# Drive_Led_Test_Bleu.net
KiCad netlist of a schematic drawn in EAGLE
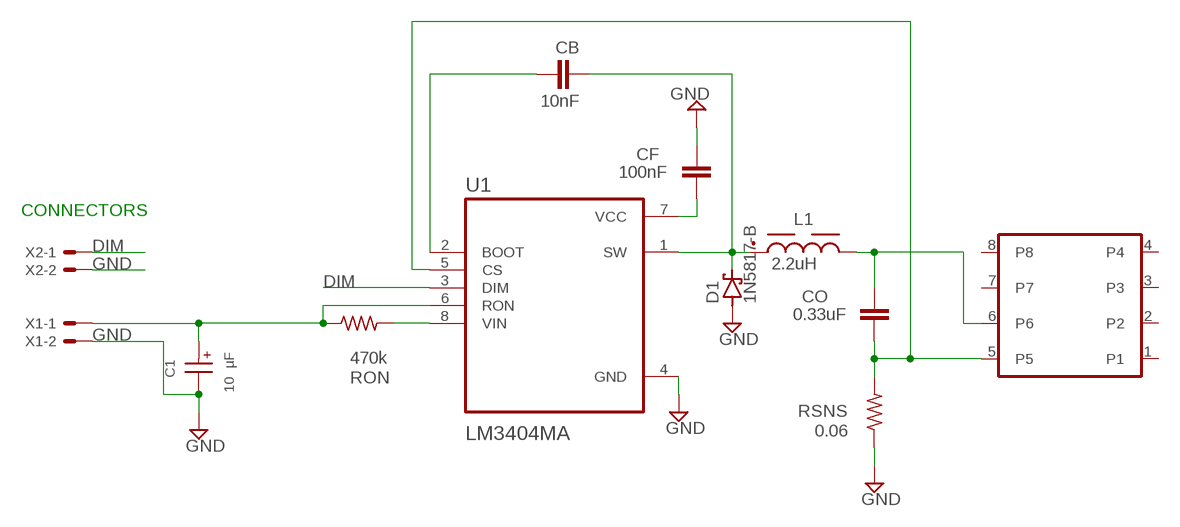
[diagram p0: schematic, sheet 1]

(export (version "E")
  (design (tool "Eeschema 10.0.6"))
  (components
    (comp (ref "C1")
      (value "10 µF")
      (footprint "eagle-import:WCAP-ASLL_4X5.5(DXL)")
      (libsource (lib "eagle-import") (part "WCAP-ASLL_4X5.5_865060440001"))
    )
    (comp (ref "CB")
      (value "10nF")
      (footprint "eagle-import:C0603")
      (libsource (lib "eagle-import") (part "C-EUC0603"))
    )
    (comp (ref "CF")
      (value "100nF")
      (footprint "eagle-import:C0603")
      (libsource (lib "eagle-import") (part "C-EUC0603"))
    )
    (comp (ref "CO")
      (value "0.33uF")
      (footprint "eagle-import:C0603")
      (libsource (lib "eagle-import") (part "C-EUC0603"))
    )
    (comp (ref "D1")
      (value "1N5817-B")
      (footprint "eagle-import:DO41-7.6")
      (libsource (lib "eagle-import") (part "1N5817-B"))
    )
    (comp (ref "L1")
      (value "2.2uH")
      (footprint "eagle-import:WE-PDA_1260")
      (libsource (lib "eagle-import") (part "WE-PDA_1260_784771022"))
    )
    (comp (ref "RON")
      (value "470k")
      (footprint "eagle-import:R0603")
      (libsource (lib "eagle-import") (part "R-US_R0603"))
    )
    (comp (ref "RSNS")
      (value "0.06")
      (footprint "eagle-import:R0603")
      (libsource (lib "eagle-import") (part "R-US_R0603"))
    )
    (comp (ref "U$1")
      (value "LE_RTDUW_S2WM_DEVICE")
      (footprint "eagle-import:LE_RTDUW_S2WM_FOOTPRINT")
      (libsource (lib "eagle-import") (part "LE_RTDUW_S2WM_DEVICE"))
    )
    (comp (ref "U1")
      (value "LM3404MA")
      (footprint "eagle-import:SOIC127P599X175-8N")
      (fields (field (name "MF") "Texas Instruments") (field (name "MP") "LM3404MA/NOPB"))
      (libsource (lib "eagle-import") (part "LM3404MA"))
    )
    (comp (ref "X1")
      (value "22-23-2021")
      (footprint "eagle-import:22-23-2021")
      (fields (field (name "MF") "MOLEX"))
      (libsource (lib "eagle-import") (part "22-23-2021"))
    )
    (comp (ref "X2")
      (value "22-23-2021")
      (footprint "eagle-import:22-23-2021")
      (fields (field (name "MF") "MOLEX"))
      (libsource (lib "eagle-import") (part "22-23-2021"))
    )
  )
  (nets
    (net (code "1") (name "/DIM") (class "Default")
      (node (ref "U1") (pin "3") (pinfunction "DIM_3") (pintype "input"))
      (node (ref "X2") (pin "1") (pinfunction "S_1") (pintype "passive"))
    )
    (net (code "2") (name "/P1") (class "Default")
      (node (ref "U$1") (pin "1") (pinfunction "P1_1") (pintype "power_in"))
    )
    (net (code "3") (name "/P2") (class "Default")
      (node (ref "U$1") (pin "2") (pinfunction "P2_2") (pintype "power_in"))
    )
    (net (code "4") (name "GND") (class "Default")
      (node (ref "C1") (pin "2") (pinfunction "-_2") (pintype "passive"))
      (node (ref "CF") (pin "1") (pinfunction "1_1") (pintype "passive"))
      (node (ref "D1") (pin "A") (pinfunction "A_A") (pintype "passive"))
      (node (ref "RSNS") (pin "1") (pinfunction "1_1") (pintype "passive"))
      (node (ref "U1") (pin "4") (pinfunction "GND_4") (pintype "power_in"))
      (node (ref "X1") (pin "2") (pinfunction "S_2") (pintype "passive"))
      (node (ref "X2") (pin "2") (pinfunction "S_2") (pintype "passive"))
    )
    (net (code "5") (name "Net-(C1-+)") (class "Default")
      (node (ref "C1") (pin "1") (pinfunction "+_1") (pintype "passive"))
      (node (ref "RON") (pin "1") (pinfunction "1_1") (pintype "passive"))
      (node (ref "U1") (pin "6") (pinfunction "RON_6") (pintype "input"))
      (node (ref "X1") (pin "1") (pinfunction "S_1") (pintype "passive"))
    )
    (net (code "6") (name "Net-(U$1-P5)") (class "Default")
      (node (ref "CO") (pin "1") (pinfunction "1_1") (pintype "passive"))
      (node (ref "RSNS") (pin "2") (pinfunction "2_2") (pintype "passive"))
      (node (ref "U$1") (pin "5") (pinfunction "P5_5") (pintype "input"))
      (node (ref "U1") (pin "5") (pinfunction "CS_5") (pintype "input"))
    )
    (net (code "7") (name "Net-(U$1-P6)") (class "Default")
      (node (ref "CO") (pin "2") (pinfunction "2_2") (pintype "passive"))
      (node (ref "L1") (pin "2") (pinfunction "2_2") (pintype "passive"))
      (node (ref "U$1") (pin "6") (pinfunction "P6_6") (pintype "bidirectional"))
    )
    (net (code "8") (name "Net-(U1-BOOT)") (class "Default")
      (node (ref "CB") (pin "1") (pinfunction "1_1") (pintype "passive"))
      (node (ref "U1") (pin "2") (pinfunction "BOOT_2") (pintype "input"))
    )
    (net (code "9") (name "Net-(U1-SW)") (class "Default")
      (node (ref "CB") (pin "2") (pinfunction "2_2") (pintype "passive"))
      (node (ref "D1") (pin "C") (pinfunction "C_C") (pintype "passive"))
      (node (ref "L1") (pin "1") (pinfunction "1_1") (pintype "passive"))
      (node (ref "U1") (pin "1") (pinfunction "SW_1") (pintype "output"))
    )
    (net (code "10") (name "Net-(U1-VCC)") (class "Default")
      (node (ref "CF") (pin "2") (pinfunction "2_2") (pintype "passive"))
      (node (ref "U1") (pin "7") (pinfunction "VCC_7") (pintype "power_in"))
    )
    (net (code "11") (name "Net-(U1-VIN)") (class "Default")
      (node (ref "RON") (pin "2") (pinfunction "2_2") (pintype "passive"))
      (node (ref "U1") (pin "8") (pinfunction "VIN_8") (pintype "input"))
    )
    (net (code "12") (name "unconnected-(U$1-P3-Pad3)") (class "Default")
      (node (ref "U$1") (pin "3") (pinfunction "P3_3") (pintype "bidirectional"))
    )
    (net (code "13") (name "unconnected-(U$1-P4-Pad4)") (class "Default")
      (node (ref "U$1") (pin "4") (pinfunction "P4_4") (pintype "bidirectional"))
    )
    (net (code "14") (name "unconnected-(U$1-P7-Pad7)") (class "Default")
      (node (ref "U$1") (pin "7") (pinfunction "P7_7") (pintype "bidirectional"))
    )
    (net (code "15") (name "unconnected-(U$1-P8-Pad8)") (class "Default")
      (node (ref "U$1") (pin "8") (pinfunction "P8_8") (pintype "bidirectional"))
    )
  )
)
